# greenhousectrl-latest-monday-no-errors-f.net
KiCad netlist of a schematic drawn in EAGLE
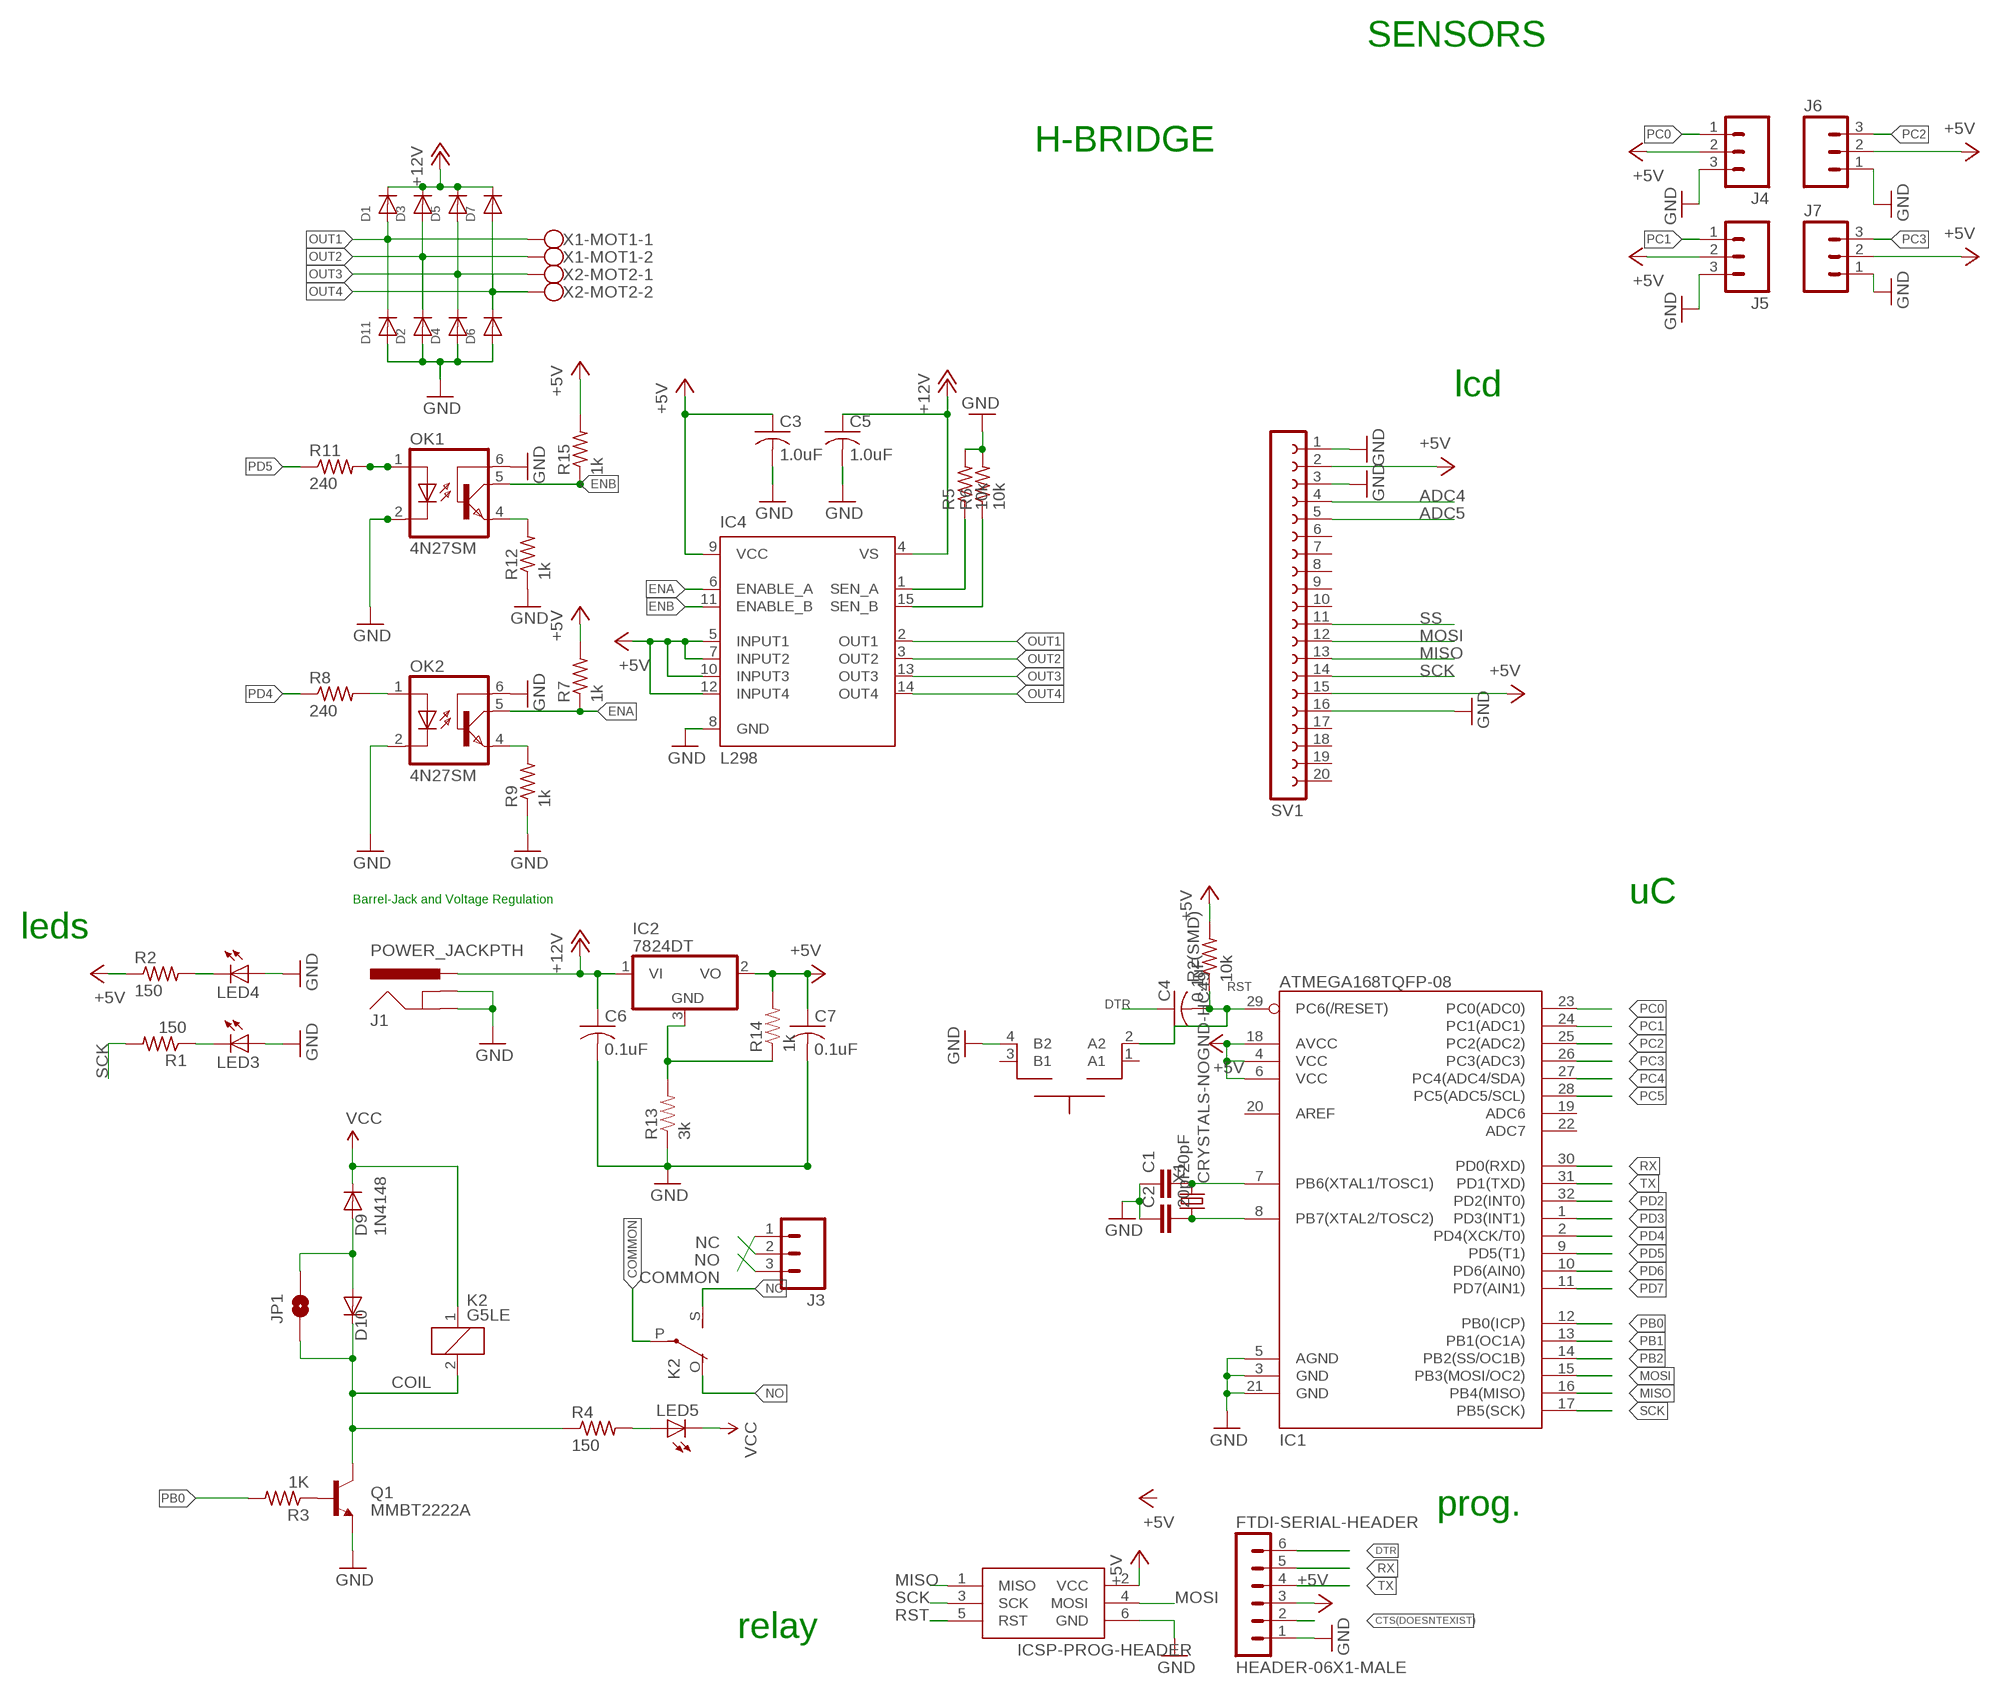
[diagram p0: schematic, sheet 1]

(export (version "E")
  (design (tool "Eeschema 10.0.6"))
  (components
    (comp (ref "C1")
      (value "20pF")
      (footprint "eagle-import:C0805")
      (libsource (lib "eagle-import") (part "C-EUC0805"))
    )
    (comp (ref "C2")
      (value "20pF")
      (footprint "eagle-import:C0805")
      (libsource (lib "eagle-import") (part "C-EUC0805"))
    )
    (comp (ref "C3")
      (value "1.0uF")
      (footprint "eagle-import:C0805")
      (libsource (lib "eagle-import") (part "C-USC0805"))
    )
    (comp (ref "C4")
      (value "0.1uF")
      (footprint "eagle-import:C0805")
      (libsource (lib "eagle-import") (part "C-USC0805"))
    )
    (comp (ref "C5")
      (value "1.0uF")
      (footprint "eagle-import:C0805")
      (libsource (lib "eagle-import") (part "C-USC0805"))
    )
    (comp (ref "C6")
      (value "0.1uF")
      (footprint "eagle-import:C0805")
      (libsource (lib "eagle-import") (part "C-USC0805"))
    )
    (comp (ref "C7")
      (value "0.1uF")
      (footprint "eagle-import:C0805")
      (libsource (lib "eagle-import") (part "C-USC0805"))
    )
    (comp (ref "D1")
      (value "DIODESOD-523")
      (footprint "eagle-import:SOD-523")
      (libsource (lib "eagle-import") (part "DIODESOD-523"))
    )
    (comp (ref "D2")
      (value "DIODESOD-523")
      (footprint "eagle-import:SOD-523")
      (libsource (lib "eagle-import") (part "DIODESOD-523"))
    )
    (comp (ref "D3")
      (value "DIODESOD-523")
      (footprint "eagle-import:SOD-523")
      (libsource (lib "eagle-import") (part "DIODESOD-523"))
    )
    (comp (ref "D4")
      (value "DIODESOD-523")
      (footprint "eagle-import:SOD-523")
      (libsource (lib "eagle-import") (part "DIODESOD-523"))
    )
    (comp (ref "D5")
      (value "DIODESOD-523")
      (footprint "eagle-import:SOD-523")
      (libsource (lib "eagle-import") (part "DIODESOD-523"))
    )
    (comp (ref "D6")
      (value "DIODESOD-523")
      (footprint "eagle-import:SOD-523")
      (libsource (lib "eagle-import") (part "DIODESOD-523"))
    )
    (comp (ref "D7")
      (value "DIODESOD-523")
      (footprint "eagle-import:SOD-523")
      (libsource (lib "eagle-import") (part "DIODESOD-523"))
    )
    (comp (ref "D9")
      (value "1N4148")
      (footprint "eagle-import:SOD-323F")
      (libsource (lib "eagle-import") (part "DIODESOD-323F"))
    )
    (comp (ref "D10")
      (value "Zener")
      (footprint "eagle-import:SOD-323F")
      (libsource (lib "eagle-import") (part "DIODESOD-323F"))
    )
    (comp (ref "D11")
      (value "DIODESOD-523")
      (footprint "eagle-import:SOD-523")
      (libsource (lib "eagle-import") (part "DIODESOD-523"))
    )
    (comp (ref "FTDI-SERIAL-HEADER")
      (value "HEADER-06X1-MALE")
      (footprint "eagle-import:06X1-PTH")
      (libsource (lib "eagle-import") (part "HEADER-06X1?-MALE"))
    )
    (comp (ref "IC1")
      (value "ATMEGA168TQFP-08")
      (footprint "eagle-import:TQFP32-08")
      (libsource (lib "eagle-import") (part "ATMEGA168TQFP-08"))
    )
    (comp (ref "IC2")
      (value "7824DT")
      (footprint "eagle-import:TO252")
      (libsource (lib "eagle-import") (part "78DT24"))
    )
    (comp (ref "IC4")
      (value "L298")
      (footprint "eagle-import:MULTIWATT-15")
      (fields (field (name "MPN") "L298N"))
      (libsource (lib "eagle-import") (part "L298"))
    )
    (comp (ref "ICSP-PROG-HEADER")
      (value "AVRISP-6")
      (footprint "eagle-import:AVRISP")
      (libsource (lib "eagle-import") (part "AVRISP-6"))
    )
    (comp (ref "J1")
      (value "POWER_JACKPTH")
      (footprint "eagle-import:POWER_JACK_PTH")
      (libsource (lib "eagle-import") (part "POWER_JACKPTH"))
    )
    (comp (ref "J3")
      (value "M03-SCREW-5MM")
      (footprint "eagle-import:SCREWTERMINAL-5MM-3")
      (libsource (lib "eagle-import") (part "M03-SCREW-5MM"))
    )
    (comp (ref "J4")
      (value "M03SCREW_LOCK")
      (footprint "eagle-import:SCREWTERMINAL-3.5MM-3_LOCK.007S")
      (libsource (lib "eagle-import") (part "M03SCREW_LOCK"))
    )
    (comp (ref "J5")
      (value "M03SCREW_LOCK")
      (footprint "eagle-import:SCREWTERMINAL-3.5MM-3_LOCK.007S")
      (libsource (lib "eagle-import") (part "M03SCREW_LOCK"))
    )
    (comp (ref "J6")
      (value "M03SCREW_LOCK")
      (footprint "eagle-import:SCREWTERMINAL-3.5MM-3_LOCK.007S")
      (libsource (lib "eagle-import") (part "M03SCREW_LOCK"))
    )
    (comp (ref "J7")
      (value "M03SCREW_LOCK")
      (footprint "eagle-import:SCREWTERMINAL-3.5MM-3_LOCK.007S")
      (libsource (lib "eagle-import") (part "M03SCREW_LOCK"))
    )
    (comp (ref "JP1")
      (value "JUMPER-PAD-2-NOYES_SILK")
      (footprint "eagle-import:PAD-JUMPER-2-NO_YES_SILK")
      (libsource (lib "eagle-import") (part "JUMPER-PAD-2-NOYES_SILK"))
    )
    (comp (ref "K2")
      (value "G5LE")
      (footprint "eagle-import:G5LE")
      (libsource (lib "eagle-import") (part "G5LE"))
    )
    (comp (ref "LED3")
      (value "LEDCHIP-LED0805")
      (footprint "eagle-import:CHIP-LED0805")
      (libsource (lib "eagle-import") (part "LEDCHIP-LED0805"))
    )
    (comp (ref "LED4")
      (value "LEDCHIP-LED0805")
      (footprint "eagle-import:CHIP-LED0805")
      (libsource (lib "eagle-import") (part "LEDCHIP-LED0805"))
    )
    (comp (ref "LED5")
      (value "LEDCHIP-LED0805")
      (footprint "eagle-import:CHIP-LED0805")
      (libsource (lib "eagle-import") (part "LEDCHIP-LED0805"))
    )
    (comp (ref "OK1")
      (value "4N27SM")
      (footprint "eagle-import:DIL6-SMD")
      (fields (field (name "MF") "FAIRCHILD SEMICONDUCTOR") (field (name "MPN") "4N27S-M"))
      (libsource (lib "eagle-import") (part "4N?MS27"))
    )
    (comp (ref "OK2")
      (value "4N27SM")
      (footprint "eagle-import:DIL6-SMD")
      (fields (field (name "MF") "FAIRCHILD SEMICONDUCTOR") (field (name "MPN") "4N27S-M"))
      (libsource (lib "eagle-import") (part "4N?MS27"))
    )
    (comp (ref "Q1")
      (value "MMBT2222A")
      (footprint "eagle-import:SOT23-3")
      (libsource (lib "eagle-import") (part "TRANSISTOR_NPNMMBT2222A"))
    )
    (comp (ref "R1")
      (value "150")
      (footprint "eagle-import:M0805")
      (libsource (lib "eagle-import") (part "R-US_M0805"))
    )
    (comp (ref "R2")
      (value "150")
      (footprint "eagle-import:M0805")
      (libsource (lib "eagle-import") (part "R-US_M0805"))
    )
    (comp (ref "R2(SMD)")
      (value "10k")
      (footprint "eagle-import:M0805")
      (libsource (lib "eagle-import") (part "R-US_M0805"))
    )
    (comp (ref "R3")
      (value "1K")
      (footprint "eagle-import:M0805")
      (libsource (lib "eagle-import") (part "R-US_M0805"))
    )
    (comp (ref "R4")
      (value "150")
      (footprint "eagle-import:M0805")
      (libsource (lib "eagle-import") (part "R-US_M0805"))
    )
    (comp (ref "R5")
      (value "10k")
      (footprint "eagle-import:M0805")
      (libsource (lib "eagle-import") (part "R-US_M0805"))
    )
    (comp (ref "R6")
      (value "10k")
      (footprint "eagle-import:M0805")
      (libsource (lib "eagle-import") (part "R-US_M0805"))
    )
    (comp (ref "R7")
      (value "1k")
      (footprint "eagle-import:M0805")
      (libsource (lib "eagle-import") (part "R-US_M0805"))
    )
    (comp (ref "R8")
      (value "240")
      (footprint "eagle-import:M0805")
      (libsource (lib "eagle-import") (part "R-US_M0805"))
    )
    (comp (ref "R9")
      (value "1k")
      (footprint "eagle-import:M0805")
      (libsource (lib "eagle-import") (part "R-US_M0805"))
    )
    (comp (ref "R11")
      (value "240")
      (footprint "eagle-import:M0805")
      (libsource (lib "eagle-import") (part "R-US_M0805"))
    )
    (comp (ref "R12")
      (value "1k")
      (footprint "eagle-import:M0805")
      (libsource (lib "eagle-import") (part "R-US_M0805"))
    )
    (comp (ref "R13")
      (value "3k")
      (footprint "eagle-import:0402-RES")
      (libsource (lib "eagle-import") (part "RESISTOR0402"))
    )
    (comp (ref "R14")
      (value "1k")
      (footprint "eagle-import:0402-RES")
      (libsource (lib "eagle-import") (part "RESISTOR0402"))
    )
    (comp (ref "R15")
      (value "1k")
      (footprint "eagle-import:M0805")
      (libsource (lib "eagle-import") (part "R-US_M0805"))
    )
    (comp (ref "SV1")
      (value "FE20-1")
      (footprint "eagle-import:FE20")
      (libsource (lib "eagle-import") (part "FE20-1"))
    )
    (comp (ref "SW2")
      (value "MOMENTARYBUTTON")
      (footprint "eagle-import:SPST_NO_SMD")
      (libsource (lib "eagle-import") (part "MOMENTARYBUTTON"))
    )
    (comp (ref "X1")
      (value "CRYSTALS-NOGND-HC49")
      (footprint "eagle-import:HC49")
      (libsource (lib "eagle-import") (part "CRYSTALS-NOGND-HC49"))
    )
    (comp (ref "X1-MOT1")
      (value "W237-102")
      (footprint "eagle-import:W237-102")
      (fields (field (name "MPN") "237-102"))
      (libsource (lib "eagle-import") (part "W237-102"))
    )
    (comp (ref "X2-MOT2")
      (value "W237-102")
      (footprint "eagle-import:W237-102")
      (fields (field (name "MPN") "237-102"))
      (libsource (lib "eagle-import") (part "W237-102"))
    )
  )
  (nets
    (net (code "1") (name "+5V") (class "Default")
      (node (ref "C3") (pin "1") (pinfunction "1_1") (pintype "passive"))
      (node (ref "C7") (pin "1") (pinfunction "1_1") (pintype "passive"))
      (node (ref "FTDI-SERIAL-HEADER") (pin "3") (pinfunction "3_3") (pintype "passive"))
      (node (ref "IC1") (pin "18") (pinfunction "AVCC_18") (pintype "bidirectional"))
      (node (ref "IC1") (pin "4") (pinfunction "VCC_4") (pintype "bidirectional"))
      (node (ref "IC1") (pin "6") (pinfunction "VCC_6") (pintype "bidirectional"))
      (node (ref "IC2") (pin "2") (pinfunction "VO_2") (pintype "passive"))
      (node (ref "IC4") (pin "10") (pinfunction "INPUT3_10") (pintype "input"))
      (node (ref "IC4") (pin "12") (pinfunction "INPUT4_12") (pintype "input"))
      (node (ref "IC4") (pin "5") (pinfunction "INPUT1_5") (pintype "input"))
      (node (ref "IC4") (pin "7") (pinfunction "INPUT2_7") (pintype "input"))
      (node (ref "IC4") (pin "9") (pinfunction "VCC_9") (pintype "power_in"))
      (node (ref "ICSP-PROG-HEADER") (pin "2") (pinfunction "VCC_2") (pintype "power_in"))
      (node (ref "J4") (pin "2") (pinfunction "2_2") (pintype "passive"))
      (node (ref "J5") (pin "2") (pinfunction "2_2") (pintype "passive"))
      (node (ref "J6") (pin "2") (pinfunction "2_2") (pintype "passive"))
      (node (ref "J7") (pin "2") (pinfunction "2_2") (pintype "passive"))
      (node (ref "R14") (pin "2") (pinfunction "2_2") (pintype "passive"))
      (node (ref "R15") (pin "2") (pinfunction "2_2") (pintype "passive"))
      (node (ref "R2") (pin "1") (pinfunction "1_1") (pintype "passive"))
      (node (ref "R2(SMD)") (pin "2") (pinfunction "2_2") (pintype "passive"))
      (node (ref "R7") (pin "2") (pinfunction "2_2") (pintype "passive"))
      (node (ref "SV1") (pin "15") (pinfunction "15_15") (pintype "passive"))
      (node (ref "SV1") (pin "2") (pinfunction "2_2") (pintype "passive"))
    )
    (net (code "2") (name "+12V") (class "Default")
      (node (ref "C5") (pin "1") (pinfunction "1_1") (pintype "passive"))
      (node (ref "C6") (pin "1") (pinfunction "1_1") (pintype "passive"))
      (node (ref "D1") (pin "K") (pinfunction "C_K") (pintype "passive"))
      (node (ref "D3") (pin "K") (pinfunction "C_K") (pintype "passive"))
      (node (ref "D5") (pin "K") (pinfunction "C_K") (pintype "passive"))
      (node (ref "D7") (pin "K") (pinfunction "C_K") (pintype "passive"))
      (node (ref "IC2") (pin "1") (pinfunction "VI_1") (pintype "input"))
      (node (ref "IC4") (pin "4") (pinfunction "VS_4") (pintype "power_in"))
      (node (ref "J1") (pin "PWR") (pinfunction "PWR_PWR") (pintype "bidirectional"))
    )
    (net (code "3") (name "/ADC4") (class "Default")
      (node (ref "SV1") (pin "4") (pinfunction "4_4") (pintype "passive"))
    )
    (net (code "4") (name "/ADC5") (class "Default")
      (node (ref "SV1") (pin "5") (pinfunction "5_5") (pintype "passive"))
    )
    (net (code "5") (name "/COIL") (class "Default")
      (node (ref "D10") (pin "C") (pinfunction "C_C") (pintype "passive"))
      (node (ref "JP1") (pin "1") (pinfunction "1_1") (pintype "passive"))
      (node (ref "K2") (pin "2") (pinfunction "2_2") (pintype "passive"))
      (node (ref "Q1") (pin "3") (pinfunction "C_3") (pintype "passive"))
      (node (ref "R4") (pin "1") (pinfunction "1_1") (pintype "passive"))
    )
    (net (code "6") (name "/RST") (class "Default")
      (node (ref "C4") (pin "2") (pinfunction "2_2") (pintype "passive"))
      (node (ref "IC1") (pin "29") (pinfunction "PC6(/RESET)_29") (pintype "bidirectional"))
      (node (ref "ICSP-PROG-HEADER") (pin "5") (pinfunction "RST_5") (pintype "output"))
      (node (ref "R2(SMD)") (pin "1") (pinfunction "1_1") (pintype "passive"))
      (node (ref "SW2") (pin "2") (pinfunction "A2_2") (pintype "bidirectional"))
    )
    (net (code "7") (name "/SS") (class "Default")
      (node (ref "SV1") (pin "11") (pinfunction "11_11") (pintype "passive"))
    )
    (net (code "8") (name "COMMON") (class "Default")
      (node (ref "J3") (pin "1") (pinfunction "1_1") (pintype "passive"))
      (node (ref "K2") (pin "P") (pinfunction "P_P") (pintype "passive"))
    )
    (net (code "9") (name "CTS(DOESNTEXIST)") (class "Default")
      (node (ref "FTDI-SERIAL-HEADER") (pin "2") (pinfunction "2_2") (pintype "passive"))
    )
    (net (code "10") (name "DTR") (class "Default")
      (node (ref "C4") (pin "1") (pinfunction "1_1") (pintype "passive"))
      (node (ref "FTDI-SERIAL-HEADER") (pin "6") (pinfunction "6_6") (pintype "passive"))
    )
    (net (code "11") (name "ENA") (class "Default")
      (node (ref "IC4") (pin "6") (pinfunction "ENABLE_A_6") (pintype "input"))
      (node (ref "OK2") (pin "5") (pinfunction "COL_5") (pintype "passive"))
      (node (ref "R7") (pin "1") (pinfunction "1_1") (pintype "passive"))
    )
    (net (code "12") (name "ENB") (class "Default")
      (node (ref "IC4") (pin "11") (pinfunction "ENABLE_B_11") (pintype "input"))
      (node (ref "OK1") (pin "5") (pinfunction "COL_5") (pintype "passive"))
      (node (ref "R15") (pin "1") (pinfunction "1_1") (pintype "passive"))
    )
    (net (code "13") (name "GND") (class "Default")
      (node (ref "C1") (pin "1") (pinfunction "1_1") (pintype "passive"))
      (node (ref "C2") (pin "1") (pinfunction "1_1") (pintype "passive"))
      (node (ref "C3") (pin "2") (pinfunction "2_2") (pintype "passive"))
      (node (ref "C5") (pin "2") (pinfunction "2_2") (pintype "passive"))
      (node (ref "C6") (pin "2") (pinfunction "2_2") (pintype "passive"))
      (node (ref "C7") (pin "2") (pinfunction "2_2") (pintype "passive"))
      (node (ref "D11") (pin "A") (pinfunction "A_A") (pintype "passive"))
      (node (ref "D2") (pin "A") (pinfunction "A_A") (pintype "passive"))
      (node (ref "D4") (pin "A") (pinfunction "A_A") (pintype "passive"))
      (node (ref "D6") (pin "A") (pinfunction "A_A") (pintype "passive"))
      (node (ref "FTDI-SERIAL-HEADER") (pin "1") (pinfunction "1_1") (pintype "passive"))
      (node (ref "IC1") (pin "21") (pinfunction "GND_21") (pintype "bidirectional"))
      (node (ref "IC1") (pin "3") (pinfunction "GND_3") (pintype "bidirectional"))
      (node (ref "IC1") (pin "5") (pinfunction "AGND_5") (pintype "bidirectional"))
      (node (ref "IC4") (pin "8") (pinfunction "GND_8") (pintype "power_in"))
      (node (ref "ICSP-PROG-HEADER") (pin "6") (pinfunction "GND_6") (pintype "power_in"))
      (node (ref "J1") (pin "GND") (pinfunction "GND_GND") (pintype "bidirectional"))
      (node (ref "J1") (pin "GNDBREAK") (pinfunction "GNDBREAK_GNDBREAK") (pintype "bidirectional"))
      (node (ref "J4") (pin "3") (pinfunction "3_3") (pintype "passive"))
      (node (ref "J5") (pin "3") (pinfunction "3_3") (pintype "passive"))
      (node (ref "J6") (pin "1") (pinfunction "1_1") (pintype "passive"))
      (node (ref "J7") (pin "1") (pinfunction "1_1") (pintype "passive"))
      (node (ref "LED3") (pin "A") (pinfunction "A_A") (pintype "passive"))
      (node (ref "LED4") (pin "A") (pinfunction "A_A") (pintype "passive"))
      (node (ref "OK1") (pin "2") (pinfunction "C_2") (pintype "passive"))
      (node (ref "OK1") (pin "6") (pinfunction "BAS_6") (pintype "passive"))
      (node (ref "OK2") (pin "2") (pinfunction "C_2") (pintype "passive"))
      (node (ref "OK2") (pin "6") (pinfunction "BAS_6") (pintype "passive"))
      (node (ref "Q1") (pin "2") (pinfunction "E_2") (pintype "passive"))
      (node (ref "R12") (pin "1") (pinfunction "1_1") (pintype "passive"))
      (node (ref "R13") (pin "1") (pinfunction "1_1") (pintype "passive"))
      (node (ref "R5") (pin "2") (pinfunction "2_2") (pintype "passive"))
      (node (ref "R6") (pin "2") (pinfunction "2_2") (pintype "passive"))
      (node (ref "R9") (pin "1") (pinfunction "1_1") (pintype "passive"))
      (node (ref "SV1") (pin "1") (pinfunction "1_1") (pintype "passive"))
      (node (ref "SV1") (pin "16") (pinfunction "16_16") (pintype "passive"))
      (node (ref "SV1") (pin "3") (pinfunction "3_3") (pintype "passive"))
      (node (ref "SW2") (pin "4") (pinfunction "B2_4") (pintype "bidirectional"))
    )
    (net (code "14") (name "MISO") (class "Default")
      (node (ref "IC1") (pin "16") (pinfunction "PB4(MISO)_16") (pintype "bidirectional"))
      (node (ref "ICSP-PROG-HEADER") (pin "1") (pinfunction "MISO_1") (pintype "input"))
      (node (ref "SV1") (pin "13") (pinfunction "13_13") (pintype "passive"))
    )
    (net (code "15") (name "MOSI") (class "Default")
      (node (ref "IC1") (pin "15") (pinfunction "PB3(MOSI/OC2)_15") (pintype "bidirectional"))
      (node (ref "ICSP-PROG-HEADER") (pin "4") (pinfunction "MOSI_4") (pintype "output"))
      (node (ref "SV1") (pin "12") (pinfunction "12_12") (pintype "passive"))
    )
    (net (code "16") (name "NC") (class "Default")
      (node (ref "J3") (pin "2") (pinfunction "2_2") (pintype "passive"))
      (node (ref "K2") (pin "S") (pinfunction "S_S") (pintype "passive"))
    )
    (net (code "17") (name "NO") (class "Default")
      (node (ref "J3") (pin "3") (pinfunction "3_3") (pintype "passive"))
      (node (ref "K2") (pin "O") (pinfunction "O_O") (pintype "passive"))
    )
    (net (code "18") (name "Net-(D10-PadA)") (class "Default")
      (node (ref "D10") (pin "A") (pinfunction "A_A") (pintype "passive"))
      (node (ref "D9") (pin "A") (pinfunction "A_A") (pintype "passive"))
      (node (ref "JP1") (pin "2") (pinfunction "2_2") (pintype "passive"))
    )
    (net (code "19") (name "Net-(IC1-PB6(XTAL1{slash}TOSC1))") (class "Default")
      (node (ref "C1") (pin "2") (pinfunction "2_2") (pintype "passive"))
      (node (ref "IC1") (pin "7") (pinfunction "PB6(XTAL1/TOSC1)_7") (pintype "bidirectional"))
      (node (ref "X1") (pin "2") (pinfunction "2_2") (pintype "passive"))
    )
    (net (code "20") (name "Net-(IC1-PB7(XTAL2{slash}TOSC2))") (class "Default")
      (node (ref "C2") (pin "2") (pinfunction "2_2") (pintype "passive"))
      (node (ref "IC1") (pin "8") (pinfunction "PB7(XTAL2/TOSC2)_8") (pintype "bidirectional"))
      (node (ref "X1") (pin "1") (pinfunction "1_1") (pintype "passive"))
    )
    (net (code "21") (name "Net-(IC2-GND)") (class "Default")
      (node (ref "IC2") (pin "3") (pinfunction "GND_3") (pintype "passive"))
      (node (ref "R13") (pin "2") (pinfunction "2_2") (pintype "passive"))
      (node (ref "R14") (pin "1") (pinfunction "1_1") (pintype "passive"))
    )
    (net (code "22") (name "Net-(IC4-SEN_A)") (class "Default")
      (node (ref "IC4") (pin "1") (pinfunction "SEN_A_1") (pintype "input"))
      (node (ref "R5") (pin "1") (pinfunction "1_1") (pintype "passive"))
    )
    (net (code "23") (name "Net-(IC4-SEN_B)") (class "Default")
      (node (ref "IC4") (pin "15") (pinfunction "SEN_B_15") (pintype "input"))
      (node (ref "R6") (pin "1") (pinfunction "1_1") (pintype "passive"))
    )
    (net (code "24") (name "Net-(LED3-PadC)") (class "Default")
      (node (ref "LED3") (pin "C") (pinfunction "C_C") (pintype "passive"))
      (node (ref "R1") (pin "1") (pinfunction "1_1") (pintype "passive"))
    )
    (net (code "25") (name "Net-(LED4-PadC)") (class "Default")
      (node (ref "LED4") (pin "C") (pinfunction "C_C") (pintype "passive"))
      (node (ref "R2") (pin "2") (pinfunction "2_2") (pintype "passive"))
    )
    (net (code "26") (name "Net-(LED5-PadA)") (class "Default")
      (node (ref "LED5") (pin "A") (pinfunction "A_A") (pintype "passive"))
      (node (ref "R4") (pin "2") (pinfunction "2_2") (pintype "passive"))
    )
    (net (code "27") (name "Net-(OK1-A)") (class "Default")
      (node (ref "OK1") (pin "1") (pinfunction "A_1") (pintype "passive"))
      (node (ref "R11") (pin "2") (pinfunction "2_2") (pintype "passive"))
    )
    (net (code "28") (name "Net-(OK1-EMI)") (class "Default")
      (node (ref "OK1") (pin "4") (pinfunction "EMI_4") (pintype "passive"))
      (node (ref "R12") (pin "2") (pinfunction "2_2") (pintype "passive"))
    )
    (net (code "29") (name "Net-(OK2-A)") (class "Default")
      (node (ref "OK2") (pin "1") (pinfunction "A_1") (pintype "passive"))
      (node (ref "R8") (pin "2") (pinfunction "2_2") (pintype "passive"))
    )
    (net (code "30") (name "Net-(OK2-EMI)") (class "Default")
      (node (ref "OK2") (pin "4") (pinfunction "EMI_4") (pintype "passive"))
      (node (ref "R9") (pin "2") (pinfunction "2_2") (pintype "passive"))
    )
    (net (code "31") (name "Net-(Q1-B)") (class "Default")
      (node (ref "Q1") (pin "1") (pinfunction "B_1") (pintype "passive"))
      (node (ref "R3") (pin "1") (pinfunction "1_1") (pintype "passive"))
    )
    (net (code "32") (name "OUT1") (class "Default")
      (node (ref "D1") (pin "A") (pinfunction "A_A") (pintype "passive"))
      (node (ref "D11") (pin "K") (pinfunction "C_K") (pintype "passive"))
      (node (ref "IC4") (pin "2") (pinfunction "OUT1_2") (pintype "output"))
      (node (ref "X1-MOT1") (pin "1") (pinfunction "KL_1") (pintype "passive"))
    )
    (net (code "33") (name "OUT2") (class "Default")
      (node (ref "D2") (pin "K") (pinfunction "C_K") (pintype "passive"))
      (node (ref "D3") (pin "A") (pinfunction "A_A") (pintype "passive"))
      (node (ref "IC4") (pin "3") (pinfunction "OUT2_3") (pintype "output"))
      (node (ref "X1-MOT1") (pin "2") (pinfunction "KL_2") (pintype "passive"))
    )
    (net (code "34") (name "OUT3") (class "Default")
      (node (ref "D4") (pin "K") (pinfunction "C_K") (pintype "passive"))
      (node (ref "D5") (pin "A") (pinfunction "A_A") (pintype "passive"))
      (node (ref "IC4") (pin "13") (pinfunction "OUT3_13") (pintype "output"))
      (node (ref "X2-MOT2") (pin "1") (pinfunction "KL_1") (pintype "passive"))
    )
    (net (code "35") (name "OUT4") (class "Default")
      (node (ref "D6") (pin "K") (pinfunction "C_K") (pintype "passive"))
      (node (ref "D7") (pin "A") (pinfunction "A_A") (pintype "passive"))
      (node (ref "IC4") (pin "14") (pinfunction "OUT4_14") (pintype "output"))
      (node (ref "X2-MOT2") (pin "2") (pinfunction "KL_2") (pintype "passive"))
    )
    (net (code "36") (name "PB0") (class "Default")
      (node (ref "IC1") (pin "12") (pinfunction "PB0(ICP)_12") (pintype "bidirectional"))
      (node (ref "R3") (pin "2") (pinfunction "2_2") (pintype "passive"))
    )
    (net (code "37") (name "PB1") (class "Default")
      (node (ref "IC1") (pin "13") (pinfunction "PB1(OC1A)_13") (pintype "bidirectional"))
    )
    (net (code "38") (name "PB2") (class "Default")
      (node (ref "IC1") (pin "14") (pinfunction "PB2(SS/OC1B)_14") (pintype "bidirectional"))
    )
    (net (code "39") (name "PC0") (class "Default")
      (node (ref "IC1") (pin "23") (pinfunction "PC0(ADC0)_23") (pintype "bidirectional"))
      (node (ref "J4") (pin "1") (pinfunction "1_1") (pintype "passive"))
    )
    (net (code "40") (name "PC1") (class "Default")
      (node (ref "IC1") (pin "24") (pinfunction "PC1(ADC1)_24") (pintype "bidirectional"))
      (node (ref "J5") (pin "1") (pinfunction "1_1") (pintype "passive"))
    )
    (net (code "41") (name "PC2") (class "Default")
      (node (ref "IC1") (pin "25") (pinfunction "PC2(ADC2)_25") (pintype "bidirectional"))
      (node (ref "J6") (pin "3") (pinfunction "3_3") (pintype "passive"))
    )
    (net (code "42") (name "PC3") (class "Default")
      (node (ref "IC1") (pin "26") (pinfunction "PC3(ADC3)_26") (pintype "bidirectional"))
      (node (ref "J7") (pin "3") (pinfunction "3_3") (pintype "passive"))
    )
    (net (code "43") (name "PC4") (class "Default")
      (node (ref "IC1") (pin "27") (pinfunction "PC4(ADC4/SDA)_27") (pintype "bidirectional"))
    )
    (net (code "44") (name "PC5") (class "Default")
      (node (ref "IC1") (pin "28") (pinfunction "PC5(ADC5/SCL)_28") (pintype "bidirectional"))
    )
    (net (code "45") (name "PD2") (class "Default")
      (node (ref "IC1") (pin "32") (pinfunction "PD2(INT0)_32") (pintype "bidirectional"))
    )
    (net (code "46") (name "PD3") (class "Default")
      (node (ref "IC1") (pin "1") (pinfunction "PD3(INT1)_1") (pintype "bidirectional"))
    )
    (net (code "47") (name "PD4") (class "Default")
      (node (ref "IC1") (pin "2") (pinfunction "PD4(XCK/T0)_2") (pintype "bidirectional"))
      (node (ref "R8") (pin "1") (pinfunction "1_1") (pintype "passive"))
    )
    (net (code "48") (name "PD5") (class "Default")
      (node (ref "IC1") (pin "9") (pinfunction "PD5(T1)_9") (pintype "bidirectional"))
      (node (ref "R11") (pin "1") (pinfunction "1_1") (pintype "passive"))
    )
    (net (code "49") (name "PD6") (class "Default")
      (node (ref "IC1") (pin "10") (pinfunction "PD6(AIN0)_10") (pintype "bidirectional"))
    )
    (net (code "50") (name "PD7") (class "Default")
      (node (ref "IC1") (pin "11") (pinfunction "PD7(AIN1)_11") (pintype "bidirectional"))
    )
    (net (code "51") (name "RX") (class "Default")
      (node (ref "FTDI-SERIAL-HEADER") (pin "5") (pinfunction "5_5") (pintype "passive"))
      (node (ref "IC1") (pin "30") (pinfunction "PD0(RXD)_30") (pintype "bidirectional"))
    )
    (net (code "52") (name "SCK") (class "Default")
      (node (ref "IC1") (pin "17") (pinfunction "PB5(SCK)_17") (pintype "bidirectional"))
      (node (ref "ICSP-PROG-HEADER") (pin "3") (pinfunction "SCK_3") (pintype "output"))
      (node (ref "R1") (pin "2") (pinfunction "2_2") (pintype "passive"))
      (node (ref "SV1") (pin "14") (pinfunction "14_14") (pintype "passive"))
    )
    (net (code "53") (name "TX") (class "Default")
      (node (ref "FTDI-SERIAL-HEADER") (pin "4") (pinfunction "4_4") (pintype "passive"))
      (node (ref "IC1") (pin "31") (pinfunction "PD1(TXD)_31") (pintype "bidirectional"))
    )
    (net (code "54") (name "VCC") (class "Default")
      (node (ref "D9") (pin "C") (pinfunction "C_C") (pintype "passive"))
      (node (ref "K2") (pin "1") (pinfunction "1_1") (pintype "passive"))
      (node (ref "LED5") (pin "C") (pinfunction "C_C") (pintype "passive"))
    )
    (net (code "55") (name "unconnected-(IC1-ADC6-Pad19)") (class "Default")
      (node (ref "IC1") (pin "19") (pinfunction "ADC6_19") (pintype "bidirectional"))
    )
    (net (code "56") (name "unconnected-(IC1-ADC7-Pad22)") (class "Default")
      (node (ref "IC1") (pin "22") (pinfunction "ADC7_22") (pintype "bidirectional"))
    )
    (net (code "57") (name "unconnected-(IC1-AREF-Pad20)") (class "Default")
      (node (ref "IC1") (pin "20") (pinfunction "AREF_20") (pintype "bidirectional"))
    )
    (net (code "58") (name "unconnected-(SV1-Pad6)") (class "Default")
      (node (ref "SV1") (pin "6") (pinfunction "6_6") (pintype "passive"))
    )
    (net (code "59") (name "unconnected-(SV1-Pad7)") (class "Default")
      (node (ref "SV1") (pin "7") (pinfunction "7_7") (pintype "passive"))
    )
    (net (code "60") (name "unconnected-(SV1-Pad8)") (class "Default")
      (node (ref "SV1") (pin "8") (pinfunction "8_8") (pintype "passive"))
    )
    (net (code "61") (name "unconnected-(SV1-Pad9)") (class "Default")
      (node (ref "SV1") (pin "9") (pinfunction "9_9") (pintype "passive"))
    )
    (net (code "62") (name "unconnected-(SV1-Pad10)") (class "Default")
      (node (ref "SV1") (pin "10") (pinfunction "10_10") (pintype "passive"))
    )
    (net (code "63") (name "unconnected-(SV1-Pad17)") (class "Default")
      (node (ref "SV1") (pin "17") (pinfunction "17_17") (pintype "passive"))
    )
    (net (code "64") (name "unconnected-(SV1-Pad18)") (class "Default")
      (node (ref "SV1") (pin "18") (pinfunction "18_18") (pintype "passive"))
    )
    (net (code "65") (name "unconnected-(SV1-Pad19)") (class "Default")
      (node (ref "SV1") (pin "19") (pinfunction "19_19") (pintype "passive"))
    )
    (net (code "66") (name "unconnected-(SV1-Pad20)") (class "Default")
      (node (ref "SV1") (pin "20") (pinfunction "20_20") (pintype "passive"))
    )
    (net (code "67") (name "unconnected-(SW2-A1-Pad1)") (class "Default")
      (node (ref "SW2") (pin "1") (pinfunction "A1_1") (pintype "bidirectional"))
    )
    (net (code "68") (name "unconnected-(SW2-B1-Pad3)") (class "Default")
      (node (ref "SW2") (pin "3") (pinfunction "B1_3") (pintype "bidirectional"))
    )
  )
)
